# base-2u-motor-dimmer-driver.net
KiCad netlist of a schematic drawn in EAGLE
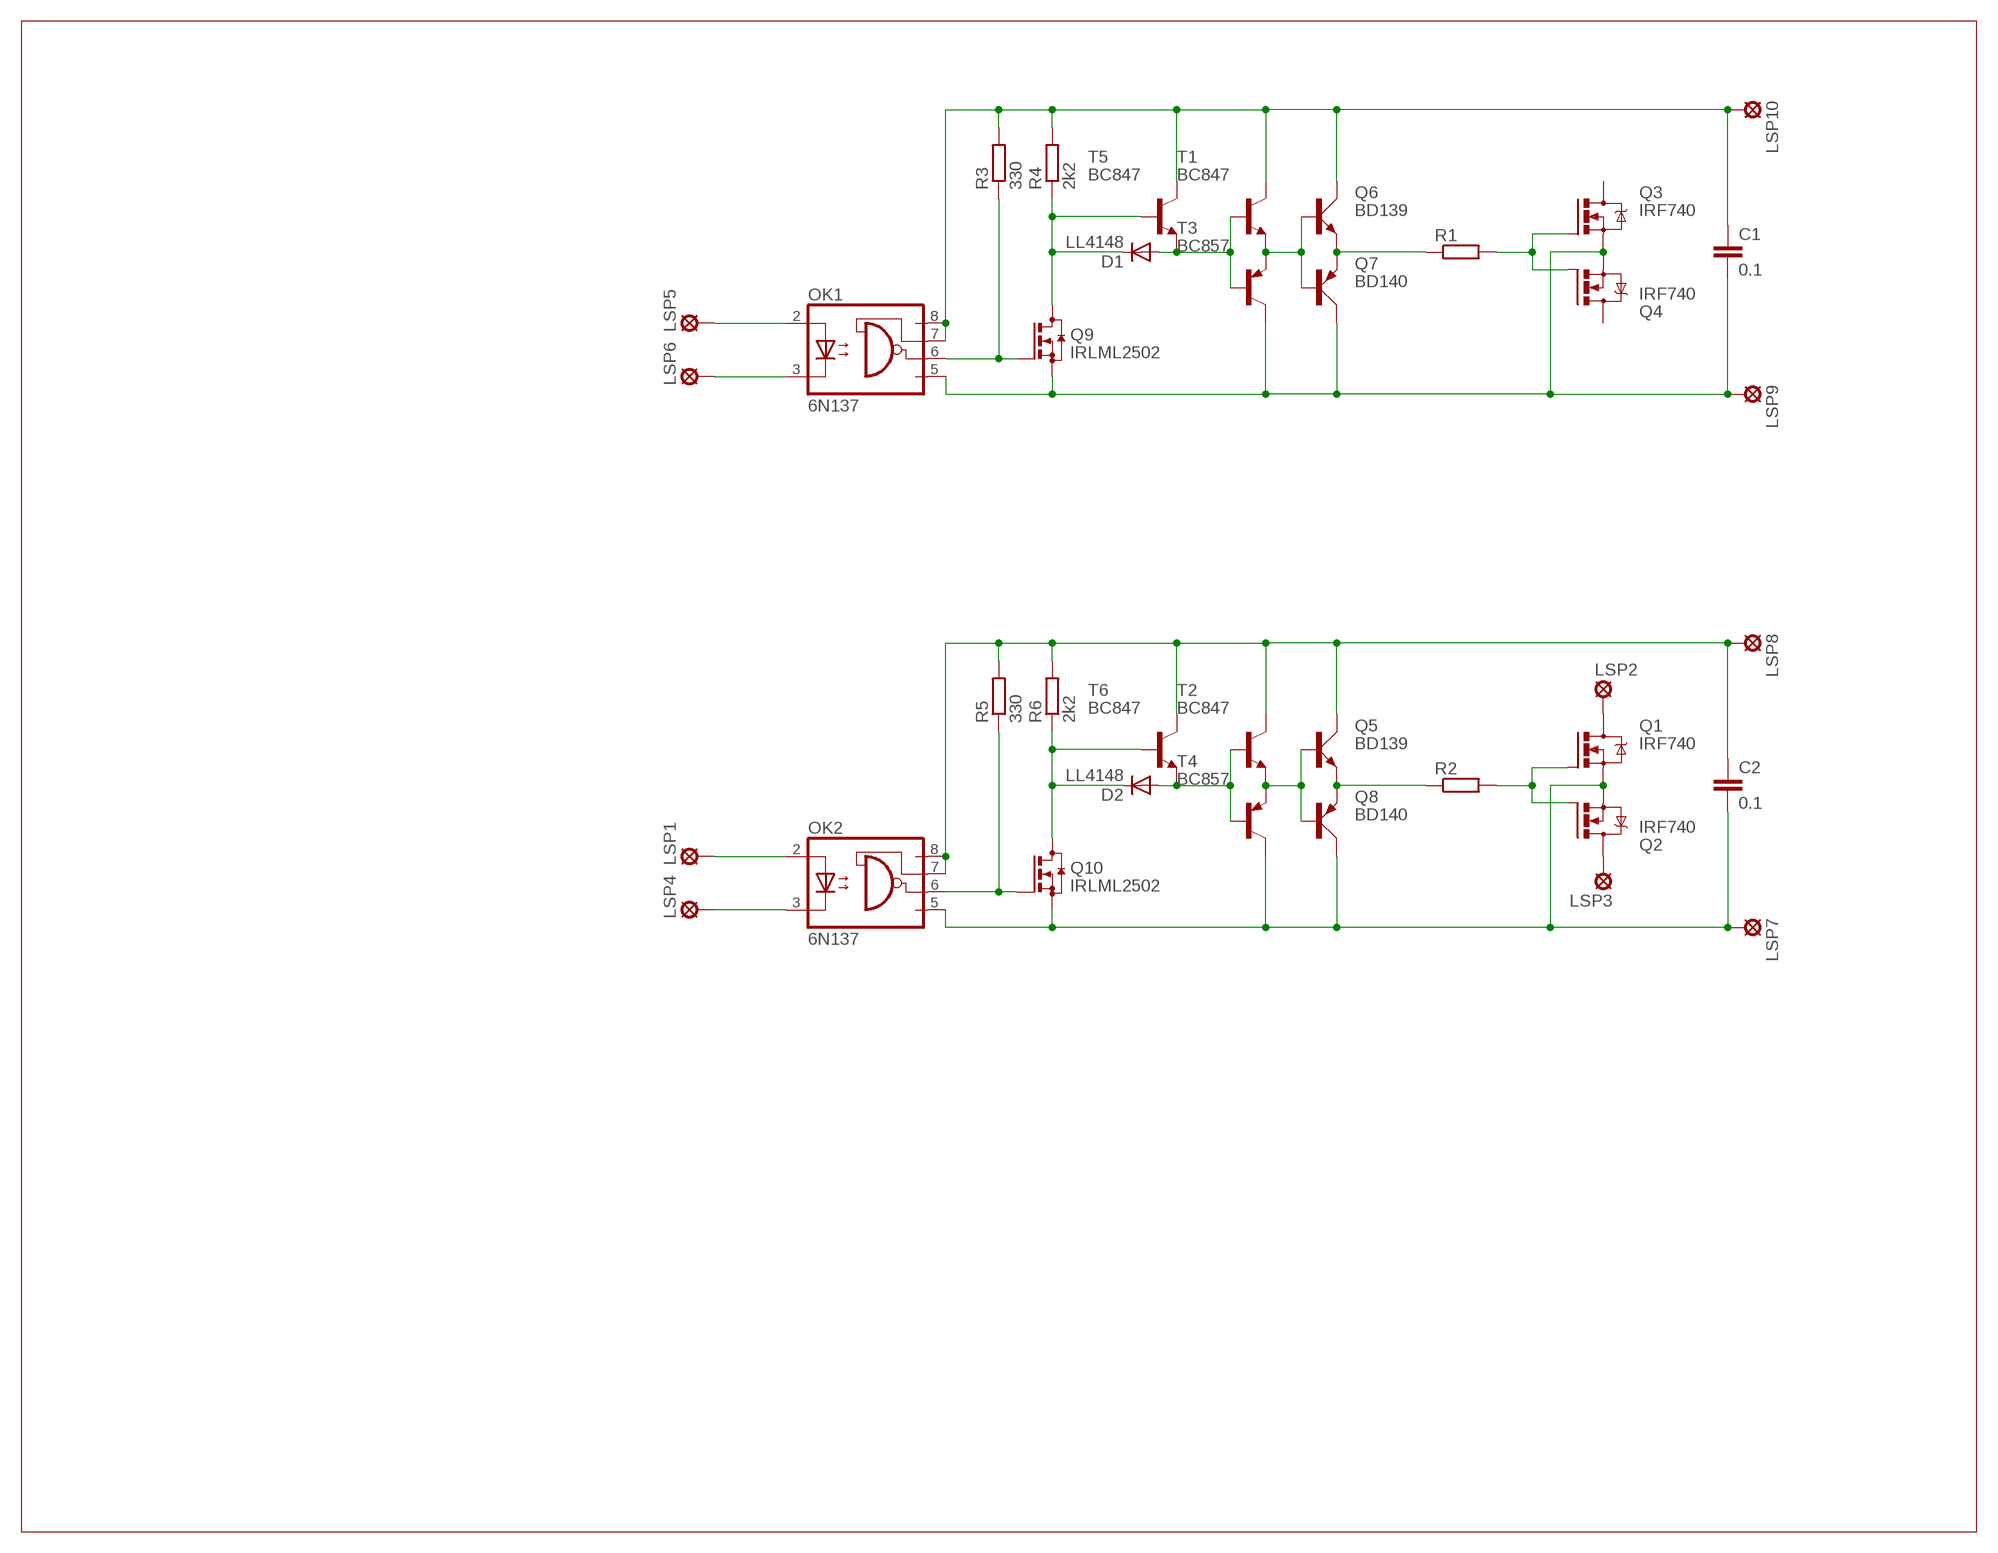
[diagram p0: schematic, sheet 1]

(export (version "E")
  (design (tool "Eeschema 10.0.6"))
  (components
    (comp (ref "C1")
      (value "0.1")
      (footprint "eagle-import:C1206")
      (libsource (lib "eagle-import") (part "C-EUC1206"))
    )
    (comp (ref "C2")
      (value "0.1")
      (footprint "eagle-import:C1206")
      (libsource (lib "eagle-import") (part "C-EUC1206"))
    )
    (comp (ref "D1")
      (value "LL4148")
      (footprint "eagle-import:SOD80C")
      (libsource (lib "eagle-import") (part "DIODE-SOD80C"))
    )
    (comp (ref "D2")
      (value "LL4148")
      (footprint "eagle-import:SOD80C")
      (libsource (lib "eagle-import") (part "DIODE-SOD80C"))
    )
    (comp (ref "LSP1")
      (value "LSP10")
      (footprint "eagle-import:LSP10")
      (libsource (lib "eagle-import") (part "LSP10"))
    )
    (comp (ref "LSP2")
      (value "LSP10")
      (footprint "eagle-import:LSP10")
      (libsource (lib "eagle-import") (part "LSP10"))
    )
    (comp (ref "LSP3")
      (value "LSP10")
      (footprint "eagle-import:LSP10")
      (libsource (lib "eagle-import") (part "LSP10"))
    )
    (comp (ref "LSP4")
      (value "LSP10")
      (footprint "eagle-import:LSP10")
      (libsource (lib "eagle-import") (part "LSP10"))
    )
    (comp (ref "LSP5")
      (value "LSP10")
      (footprint "eagle-import:LSP10")
      (libsource (lib "eagle-import") (part "LSP10"))
    )
    (comp (ref "LSP6")
      (value "LSP10")
      (footprint "eagle-import:LSP10")
      (libsource (lib "eagle-import") (part "LSP10"))
    )
    (comp (ref "LSP7")
      (value "LSP10")
      (footprint "eagle-import:LSP10")
      (libsource (lib "eagle-import") (part "LSP10"))
    )
    (comp (ref "LSP8")
      (value "LSP10")
      (footprint "eagle-import:LSP10")
      (libsource (lib "eagle-import") (part "LSP10"))
    )
    (comp (ref "LSP9")
      (value "LSP10")
      (footprint "eagle-import:LSP10")
      (libsource (lib "eagle-import") (part "LSP10"))
    )
    (comp (ref "LSP10")
      (value "LSP10")
      (footprint "eagle-import:LSP10")
      (libsource (lib "eagle-import") (part "LSP10"))
    )
    (comp (ref "OK1")
      (value "6N137")
      (footprint "eagle-import:DIL08")
      (libsource (lib "eagle-import") (part "6N137"))
    )
    (comp (ref "OK2")
      (value "6N137")
      (footprint "eagle-import:DIL08")
      (libsource (lib "eagle-import") (part "6N137"))
    )
    (comp (ref "Q1")
      (value "IRF740")
      (footprint "eagle-import:TO220BV")
      (libsource (lib "eagle-import") (part "IRF740"))
    )
    (comp (ref "Q2")
      (value "IRF740")
      (footprint "eagle-import:TO220BV")
      (libsource (lib "eagle-import") (part "IRF740"))
    )
    (comp (ref "Q3")
      (value "IRF740")
      (footprint "eagle-import:TO220BV")
      (libsource (lib "eagle-import") (part "IRF740"))
    )
    (comp (ref "Q4")
      (value "IRF740")
      (footprint "eagle-import:TO220BV")
      (libsource (lib "eagle-import") (part "IRF740"))
    )
    (comp (ref "Q5")
      (value "BD139")
      (footprint "eagle-import:TO126AV")
      (libsource (lib "eagle-import") (part "BD139"))
    )
    (comp (ref "Q6")
      (value "BD139")
      (footprint "eagle-import:TO126AV")
      (libsource (lib "eagle-import") (part "BD139"))
    )
    (comp (ref "Q7")
      (value "BD140")
      (footprint "eagle-import:TO126AV")
      (libsource (lib "eagle-import") (part "BD140"))
    )
    (comp (ref "Q8")
      (value "BD140")
      (footprint "eagle-import:TO126AV")
      (libsource (lib "eagle-import") (part "BD140"))
    )
    (comp (ref "Q9")
      (value "IRLML2502")
      (footprint "eagle-import:SOT23")
      (libsource (lib "eagle-import") (part "BSS123"))
    )
    (comp (ref "Q10")
      (value "IRLML2502")
      (footprint "eagle-import:SOT23")
      (libsource (lib "eagle-import") (part "BSS123"))
    )
    (comp (ref "R1")
      (value "R-EU_R0805")
      (footprint "eagle-import:R0805")
      (libsource (lib "eagle-import") (part "R-EU_R0805"))
    )
    (comp (ref "R2")
      (value "R-EU_R0805")
      (footprint "eagle-import:R0805")
      (libsource (lib "eagle-import") (part "R-EU_R0805"))
    )
    (comp (ref "R3")
      (value "330")
      (footprint "eagle-import:R0805")
      (libsource (lib "eagle-import") (part "R-EU_R0805"))
    )
    (comp (ref "R4")
      (value "2k2")
      (footprint "eagle-import:R0805")
      (libsource (lib "eagle-import") (part "R-EU_R0805"))
    )
    (comp (ref "R5")
      (value "330")
      (footprint "eagle-import:R0805")
      (libsource (lib "eagle-import") (part "R-EU_R0805"))
    )
    (comp (ref "R6")
      (value "2k2")
      (footprint "eagle-import:R0805")
      (libsource (lib "eagle-import") (part "R-EU_R0805"))
    )
    (comp (ref "T1")
      (value "BC847")
      (footprint "eagle-import:SOT23")
      (libsource (lib "eagle-import") (part "BC847"))
    )
    (comp (ref "T2")
      (value "BC847")
      (footprint "eagle-import:SOT23")
      (libsource (lib "eagle-import") (part "BC847"))
    )
    (comp (ref "T3")
      (value "BC857")
      (footprint "eagle-import:SOT23-BEC")
      (libsource (lib "eagle-import") (part "-PNP-SOT23-BECBC857B"))
    )
    (comp (ref "T4")
      (value "BC857")
      (footprint "eagle-import:SOT23-BEC")
      (libsource (lib "eagle-import") (part "-PNP-SOT23-BECBC857B"))
    )
    (comp (ref "T5")
      (value "BC847")
      (footprint "eagle-import:SOT23")
      (libsource (lib "eagle-import") (part "BC847"))
    )
    (comp (ref "T6")
      (value "BC847")
      (footprint "eagle-import:SOT23")
      (libsource (lib "eagle-import") (part "BC847"))
    )
  )
  (nets
    (net (code "1") (name "Net-(LSP2-PadMP)") (class "Default")
      (node (ref "LSP2") (pin "MP") (pinfunction "MP_MP") (pintype "passive"))
      (node (ref "Q1") (pin "D") (pinfunction "D_D") (pintype "passive"))
    )
    (net (code "2") (name "Net-(LSP3-PadMP)") (class "Default")
      (node (ref "LSP3") (pin "MP") (pinfunction "MP_MP") (pintype "passive"))
      (node (ref "Q2") (pin "D") (pinfunction "D_D") (pintype "passive"))
    )
    (net (code "3") (name "Net-(OK1-A)") (class "Default")
      (node (ref "LSP5") (pin "MP") (pinfunction "MP_MP") (pintype "passive"))
      (node (ref "OK1") (pin "2") (pinfunction "A_2") (pintype "passive"))
    )
    (net (code "4") (name "Net-(OK1-C)") (class "Default")
      (node (ref "LSP6") (pin "MP") (pinfunction "MP_MP") (pintype "passive"))
      (node (ref "OK1") (pin "3") (pinfunction "C_3") (pintype "passive"))
    )
    (net (code "5") (name "Net-(OK1-GND)") (class "Default")
      (node (ref "C1") (pin "2") (pinfunction "2_2") (pintype "passive"))
      (node (ref "LSP9") (pin "MP") (pinfunction "MP_MP") (pintype "passive"))
      (node (ref "OK1") (pin "5") (pinfunction "GND_5") (pintype "passive"))
      (node (ref "Q3") (pin "S") (pinfunction "S_S") (pintype "passive"))
      (node (ref "Q4") (pin "S") (pinfunction "S_S") (pintype "passive"))
      (node (ref "Q7") (pin "C") (pinfunction "C_C") (pintype "passive"))
      (node (ref "Q9") (pin "2") (pinfunction "S_2") (pintype "passive"))
      (node (ref "T3") (pin "C") (pinfunction "C_C") (pintype "passive"))
    )
    (net (code "6") (name "Net-(OK1-VCC)") (class "Default")
      (node (ref "C1") (pin "1") (pinfunction "1_1") (pintype "passive"))
      (node (ref "LSP10") (pin "MP") (pinfunction "MP_MP") (pintype "passive"))
      (node (ref "OK1") (pin "7") (pinfunction "VE_7") (pintype "passive"))
      (node (ref "OK1") (pin "8") (pinfunction "VCC_8") (pintype "passive"))
      (node (ref "Q6") (pin "C") (pinfunction "C_C") (pintype "passive"))
      (node (ref "R3") (pin "2") (pinfunction "2_2") (pintype "passive"))
      (node (ref "R4") (pin "2") (pinfunction "2_2") (pintype "passive"))
      (node (ref "T1") (pin "3") (pinfunction "C_3") (pintype "passive"))
      (node (ref "T5") (pin "3") (pinfunction "C_3") (pintype "passive"))
    )
    (net (code "7") (name "Net-(OK1-VO)") (class "Default")
      (node (ref "OK1") (pin "6") (pinfunction "VO_6") (pintype "passive"))
      (node (ref "Q9") (pin "1") (pinfunction "G_1") (pintype "passive"))
      (node (ref "R3") (pin "1") (pinfunction "1_1") (pintype "passive"))
    )
    (net (code "8") (name "Net-(OK2-A)") (class "Default")
      (node (ref "LSP1") (pin "MP") (pinfunction "MP_MP") (pintype "passive"))
      (node (ref "OK2") (pin "2") (pinfunction "A_2") (pintype "passive"))
    )
    (net (code "9") (name "Net-(OK2-C)") (class "Default")
      (node (ref "LSP4") (pin "MP") (pinfunction "MP_MP") (pintype "passive"))
      (node (ref "OK2") (pin "3") (pinfunction "C_3") (pintype "passive"))
    )
    (net (code "10") (name "Net-(OK2-GND)") (class "Default")
      (node (ref "C2") (pin "2") (pinfunction "2_2") (pintype "passive"))
      (node (ref "LSP7") (pin "MP") (pinfunction "MP_MP") (pintype "passive"))
      (node (ref "OK2") (pin "5") (pinfunction "GND_5") (pintype "passive"))
      (node (ref "Q1") (pin "S") (pinfunction "S_S") (pintype "passive"))
      (node (ref "Q10") (pin "2") (pinfunction "S_2") (pintype "passive"))
      (node (ref "Q2") (pin "S") (pinfunction "S_S") (pintype "passive"))
      (node (ref "Q8") (pin "C") (pinfunction "C_C") (pintype "passive"))
      (node (ref "T4") (pin "C") (pinfunction "C_C") (pintype "passive"))
    )
    (net (code "11") (name "Net-(OK2-VCC)") (class "Default")
      (node (ref "C2") (pin "1") (pinfunction "1_1") (pintype "passive"))
      (node (ref "LSP8") (pin "MP") (pinfunction "MP_MP") (pintype "passive"))
      (node (ref "OK2") (pin "7") (pinfunction "VE_7") (pintype "passive"))
      (node (ref "OK2") (pin "8") (pinfunction "VCC_8") (pintype "passive"))
      (node (ref "Q5") (pin "C") (pinfunction "C_C") (pintype "passive"))
      (node (ref "R5") (pin "2") (pinfunction "2_2") (pintype "passive"))
      (node (ref "R6") (pin "2") (pinfunction "2_2") (pintype "passive"))
      (node (ref "T2") (pin "3") (pinfunction "C_3") (pintype "passive"))
      (node (ref "T6") (pin "3") (pinfunction "C_3") (pintype "passive"))
    )
    (net (code "12") (name "Net-(OK2-VO)") (class "Default")
      (node (ref "OK2") (pin "6") (pinfunction "VO_6") (pintype "passive"))
      (node (ref "Q10") (pin "1") (pinfunction "G_1") (pintype "passive"))
      (node (ref "R5") (pin "1") (pinfunction "1_1") (pintype "passive"))
    )
    (net (code "13") (name "Net-(Q1-PadG)") (class "Default")
      (node (ref "Q1") (pin "G") (pinfunction "G_G") (pintype "passive"))
      (node (ref "Q2") (pin "G") (pinfunction "G_G") (pintype "passive"))
      (node (ref "R2") (pin "2") (pinfunction "2_2") (pintype "passive"))
    )
    (net (code "14") (name "Net-(Q3-PadG)") (class "Default")
      (node (ref "Q3") (pin "G") (pinfunction "G_G") (pintype "passive"))
      (node (ref "Q4") (pin "G") (pinfunction "G_G") (pintype "passive"))
      (node (ref "R1") (pin "2") (pinfunction "2_2") (pintype "passive"))
    )
    (net (code "15") (name "Net-(Q5-PadE)") (class "Default")
      (node (ref "Q5") (pin "E") (pinfunction "E_E") (pintype "passive"))
      (node (ref "Q8") (pin "E") (pinfunction "E_E") (pintype "passive"))
      (node (ref "R2") (pin "1") (pinfunction "1_1") (pintype "passive"))
    )
    (net (code "16") (name "Net-(Q6-PadE)") (class "Default")
      (node (ref "Q6") (pin "E") (pinfunction "E_E") (pintype "passive"))
      (node (ref "Q7") (pin "E") (pinfunction "E_E") (pintype "passive"))
      (node (ref "R1") (pin "1") (pinfunction "1_1") (pintype "passive"))
    )
    (net (code "17") (name "Net-(Q9-D)") (class "Default")
      (node (ref "D1") (pin "C") (pinfunction "C_C") (pintype "passive"))
      (node (ref "Q9") (pin "3") (pinfunction "D_3") (pintype "passive"))
      (node (ref "R4") (pin "1") (pinfunction "1_1") (pintype "passive"))
      (node (ref "T5") (pin "1") (pinfunction "B_1") (pintype "passive"))
    )
    (net (code "18") (name "Net-(Q10-D)") (class "Default")
      (node (ref "D2") (pin "C") (pinfunction "C_C") (pintype "passive"))
      (node (ref "Q10") (pin "3") (pinfunction "D_3") (pintype "passive"))
      (node (ref "R6") (pin "1") (pinfunction "1_1") (pintype "passive"))
      (node (ref "T6") (pin "1") (pinfunction "B_1") (pintype "passive"))
    )
    (net (code "19") (name "Net-(T1-B)") (class "Default")
      (node (ref "D1") (pin "A") (pinfunction "A_A") (pintype "passive"))
      (node (ref "T1") (pin "1") (pinfunction "B_1") (pintype "passive"))
      (node (ref "T3") (pin "B") (pinfunction "B_B") (pintype "passive"))
      (node (ref "T5") (pin "2") (pinfunction "E_2") (pintype "passive"))
    )
    (net (code "20") (name "Net-(T1-E)") (class "Default")
      (node (ref "Q6") (pin "B") (pinfunction "B_B") (pintype "passive"))
      (node (ref "Q7") (pin "B") (pinfunction "B_B") (pintype "passive"))
      (node (ref "T1") (pin "2") (pinfunction "E_2") (pintype "passive"))
      (node (ref "T3") (pin "E") (pinfunction "E_E") (pintype "passive"))
    )
    (net (code "21") (name "Net-(T2-B)") (class "Default")
      (node (ref "D2") (pin "A") (pinfunction "A_A") (pintype "passive"))
      (node (ref "T2") (pin "1") (pinfunction "B_1") (pintype "passive"))
      (node (ref "T4") (pin "B") (pinfunction "B_B") (pintype "passive"))
      (node (ref "T6") (pin "2") (pinfunction "E_2") (pintype "passive"))
    )
    (net (code "22") (name "Net-(T2-E)") (class "Default")
      (node (ref "Q5") (pin "B") (pinfunction "B_B") (pintype "passive"))
      (node (ref "Q8") (pin "B") (pinfunction "B_B") (pintype "passive"))
      (node (ref "T2") (pin "2") (pinfunction "E_2") (pintype "passive"))
      (node (ref "T4") (pin "E") (pinfunction "E_E") (pintype "passive"))
    )
    (net (code "23") (name "unconnected-(Q3-PadD)") (class "Default")
      (node (ref "Q3") (pin "D") (pinfunction "D_D") (pintype "passive"))
    )
    (net (code "24") (name "unconnected-(Q4-PadD)") (class "Default")
      (node (ref "Q4") (pin "D") (pinfunction "D_D") (pintype "passive"))
    )
  )
)
